# flarm-f4-interface.net
KiCad netlist of a schematic drawn in Altium Designer
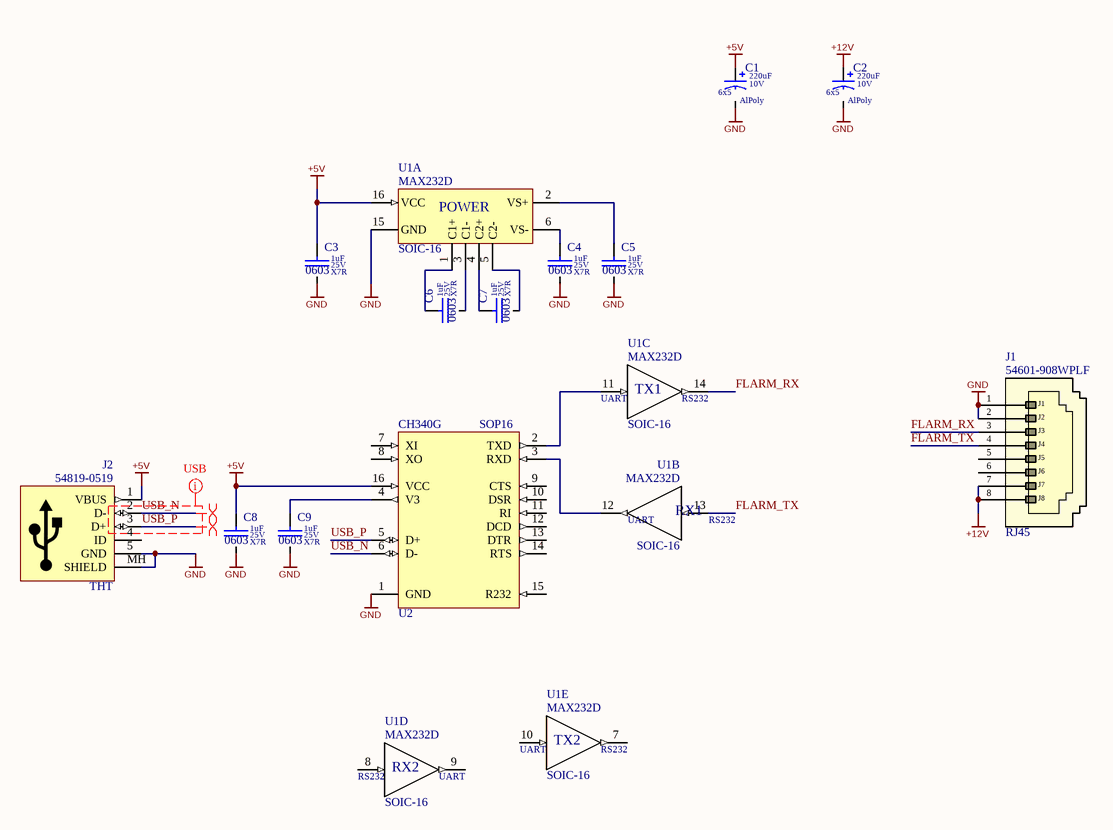
[diagram p0: flarm-f4-interface.SchDoc]

(export (version "E")
  (design (tool "Eeschema 10.0.6"))
  (components
    (comp (ref "C1")
      (value "220uF")
      (footprint "CE_D_6x5_SMD")
      (description "Polarized Capacitor")
      (fields
        (field (name "DIELECTRIC") "AlPoly")
        (field (name "SCH_FOOTPRINT") "6x5")
        (field (name "VOLTAGE") "10V")
        (field (name "PART NUMBER") "CE_220uF_10V_AlPoly_6x5_20")
        (field (name "MANUFACTURER") "Wurth Elektronik")
      )
      (libsource (lib "Library") (part "CE"))
    )
    (comp (ref "C2")
      (value "220uF")
      (footprint "CE_D_6x5_SMD")
      (description "Polarized Capacitor")
      (fields
        (field (name "DIELECTRIC") "AlPoly")
        (field (name "SCH_FOOTPRINT") "6x5")
        (field (name "VOLTAGE") "10V")
        (field (name "PART NUMBER") "CE_220uF_10V_AlPoly_6x5_20")
        (field (name "MANUFACTURER") "Wurth Elektronik")
      )
      (libsource (lib "Library") (part "CE"))
    )
    (comp (ref "C3")
      (value "1uF")
      (footprint "C_0603_1608")
      (description "Capacitor")
      (fields
        (field (name "DIELECTRIC") "X7R")
        (field (name "VOLTAGE") "25V")
        (field (name "SCH_FOOTPRINT") "0603")
        (field (name "PART NUMBER") "C_1uF_25V_X7R_0603_10")
        (field (name "MANUFACTURER") "Samsung")
      )
      (libsource (lib "Library") (part "C"))
    )
    (comp (ref "C4")
      (value "1uF")
      (footprint "C_0603_1608")
      (description "Capacitor")
      (fields
        (field (name "DIELECTRIC") "X7R")
        (field (name "VOLTAGE") "25V")
        (field (name "SCH_FOOTPRINT") "0603")
        (field (name "PART NUMBER") "C_1uF_25V_X7R_0603_10")
        (field (name "MANUFACTURER") "Samsung")
      )
      (libsource (lib "Library") (part "C"))
    )
    (comp (ref "C5")
      (value "1uF")
      (footprint "C_0603_1608")
      (description "Capacitor")
      (fields
        (field (name "DIELECTRIC") "X7R")
        (field (name "VOLTAGE") "25V")
        (field (name "SCH_FOOTPRINT") "0603")
        (field (name "PART NUMBER") "C_1uF_25V_X7R_0603_10")
        (field (name "MANUFACTURER") "Samsung")
      )
      (libsource (lib "Library") (part "C"))
    )
    (comp (ref "C6")
      (value "1uF")
      (footprint "C_0603_1608")
      (description "Capacitor")
      (fields
        (field (name "DIELECTRIC") "X7R")
        (field (name "VOLTAGE") "25V")
        (field (name "SCH_FOOTPRINT") "0603")
        (field (name "PART NUMBER") "C_1uF_25V_X7R_0603_10")
        (field (name "MANUFACTURER") "Samsung")
      )
      (libsource (lib "Library") (part "C"))
    )
    (comp (ref "C7")
      (value "1uF")
      (footprint "C_0603_1608")
      (description "Capacitor")
      (fields
        (field (name "DIELECTRIC") "X7R")
        (field (name "VOLTAGE") "25V")
        (field (name "SCH_FOOTPRINT") "0603")
        (field (name "PART NUMBER") "C_1uF_25V_X7R_0603_10")
        (field (name "MANUFACTURER") "Samsung")
      )
      (libsource (lib "Library") (part "C"))
    )
    (comp (ref "C8")
      (value "1uF")
      (footprint "C_0603_1608")
      (description "Capacitor")
      (fields
        (field (name "DIELECTRIC") "X7R")
        (field (name "VOLTAGE") "25V")
        (field (name "SCH_FOOTPRINT") "0603")
        (field (name "PART NUMBER") "C_1uF_25V_X7R_0603_10")
        (field (name "MANUFACTURER") "Samsung")
      )
      (libsource (lib "Library") (part "C"))
    )
    (comp (ref "C9")
      (value "1uF")
      (footprint "C_0603_1608")
      (description "Capacitor")
      (fields
        (field (name "DIELECTRIC") "X7R")
        (field (name "VOLTAGE") "25V")
        (field (name "SCH_FOOTPRINT") "0603")
        (field (name "PART NUMBER") "C_1uF_25V_X7R_0603_10")
        (field (name "MANUFACTURER") "Samsung")
      )
      (libsource (lib "Library") (part "C"))
    )
    (comp (ref "J1")
      (value "54601-908WPLF")
      (footprint "J_RJ45_54601-908WPLF")
      (fields
        (field (name "SCH_FOOTPRINT") "RJ45")
        (field (name "PART NUMBER") "J_RJ45_54601-908WPLF")
        (field (name "MANUFACTURER") "Amphenol")
        (field (name "Comment") "RJ45 without magnetics")
      )
      (libsource (lib "Library") (part "J_RJ45"))
    )
    (comp (ref "J2")
      (value "54819-0519")
      (footprint "J_USB_MINIB_54819-0519_THT")
      (description "USB A THT Connector")
      (fields
        (field (name "SCH_FOOTPRINT") "THT")
        (field (name "PART NUMBER") "J_USB_MINIB_54819-0519")
        (field (name "MANUFACTURER") "Molex")
      )
      (libsource (lib "Library") (part "J_USB_2.0_5pin"))
    )
    (comp (ref "U1")
      (value "MAX232D")
      (footprint "SOP16_SO16_SOIC16_4X10X6")
      (fields
        (field (name "SCH_FOOTPRINT") "SOIC-16")
        (field (name "PART NUMBER") "U_MAX232D")
        (field (name "MANUFACTURER") "Texas Instruments")
        (field (name "Comment") "MAX232D UART/RS-232 Converter")
      )
      (libsource (lib "Library") (part "U_MAX232D"))
    )
    (comp (ref "U2")
      (value "CH340G")
      (footprint "SOP16_SO16_SOIC16_4X10X6")
      (fields
        (field (name "SCH_FOOTPRINT") "SOP16")
        (field (name "PART NUMBER") "U_CH340G")
        (field (name "MANUFACTURER") "WCH")
        (field (name "Comment") "USB to serial chip")
      )
      (libsource (lib "Library") (part "U_CH340_MSOP16"))
    )
  )
  (nets
    (net (code "1") (name "+5V") (class "Default")
      (node (ref "C1") (pin "1") (pinfunction "1_1") (pintype "passive"))
      (node (ref "C3") (pin "1") (pinfunction "1_1") (pintype "passive"))
      (node (ref "C8") (pin "1") (pinfunction "1_1") (pintype "passive"))
      (node (ref "J2") (pin "1") (pinfunction "VBUS_1") (pintype "output"))
      (node (ref "U1") (pin "16") (pinfunction "VCC_16") (pintype "input"))
      (node (ref "U2") (pin "16") (pinfunction "VCC_16") (pintype "input"))
    )
    (net (code "2") (name "+12V") (class "Default")
      (node (ref "C2") (pin "1") (pinfunction "1_1") (pintype "passive"))
      (node (ref "J1") (pin "7") (pintype "passive"))
      (node (ref "J1") (pin "8") (pintype "passive"))
    )
    (net (code "3") (name "/FLARM_RX") (class "Default")
      (node (ref "J1") (pin "3") (pintype "passive"))
      (node (ref "U1") (pin "14") (pinfunction "T1OUT_14") (pintype "output"))
    )
    (net (code "4") (name "/FLARM_TX") (class "Default")
      (node (ref "J1") (pin "4") (pintype "passive"))
      (node (ref "U1") (pin "13") (pinfunction "R1IN_13") (pintype "input"))
    )
    (net (code "5") (name "/USB_N") (class "Default")
      (node (ref "J2") (pin "2") (pinfunction "D-_2") (pintype "bidirectional"))
      (node (ref "U2") (pin "6") (pinfunction "D-_6") (pintype "bidirectional"))
    )
    (net (code "6") (name "/USB_P") (class "Default")
      (node (ref "J2") (pin "3") (pinfunction "D+_3") (pintype "bidirectional"))
      (node (ref "U2") (pin "5") (pinfunction "D+_5") (pintype "bidirectional"))
    )
    (net (code "7") (name "GND") (class "Default")
      (node (ref "C1") (pin "2") (pinfunction "2_2") (pintype "passive"))
      (node (ref "C2") (pin "2") (pinfunction "2_2") (pintype "passive"))
      (node (ref "C3") (pin "2") (pinfunction "2_2") (pintype "passive"))
      (node (ref "C4") (pin "2") (pinfunction "2_2") (pintype "passive"))
      (node (ref "C5") (pin "2") (pinfunction "2_2") (pintype "passive"))
      (node (ref "C8") (pin "2") (pinfunction "2_2") (pintype "passive"))
      (node (ref "C9") (pin "2") (pinfunction "2_2") (pintype "passive"))
      (node (ref "J1") (pin "1") (pintype "passive"))
      (node (ref "J1") (pin "2") (pintype "passive"))
      (node (ref "J2") (pin "5") (pinfunction "GND_5") (pintype "power_in"))
      (node (ref "J2") (pin "MH") (pinfunction "SHIELD_MH") (pintype "passive"))
      (node (ref "U1") (pin "15") (pinfunction "GND_15") (pintype "power_in"))
      (node (ref "U2") (pin "1") (pinfunction "GND_1") (pintype "power_in"))
    )
    (net (code "8") (name "Net-(U1A-C1+)") (class "Default")
      (node (ref "C6") (pin "1") (pinfunction "1_1") (pintype "passive"))
      (node (ref "U1") (pin "1") (pinfunction "C1+_1") (pintype "passive"))
    )
    (net (code "9") (name "Net-(U1A-C1-)") (class "Default")
      (node (ref "C6") (pin "2") (pinfunction "2_2") (pintype "passive"))
      (node (ref "U1") (pin "3") (pinfunction "C1-_3") (pintype "passive"))
    )
    (net (code "10") (name "Net-(U1A-C2+)") (class "Default")
      (node (ref "C7") (pin "1") (pinfunction "1_1") (pintype "passive"))
      (node (ref "U1") (pin "4") (pinfunction "C2+_4") (pintype "passive"))
    )
    (net (code "11") (name "Net-(U1A-C2-)") (class "Default")
      (node (ref "C7") (pin "2") (pinfunction "2_2") (pintype "passive"))
      (node (ref "U1") (pin "5") (pinfunction "C2-_5") (pintype "passive"))
    )
    (net (code "12") (name "Net-(U1A-VS+)") (class "Default")
      (node (ref "C5") (pin "1") (pinfunction "1_1") (pintype "passive"))
      (node (ref "U1") (pin "2") (pinfunction "VS+_2") (pintype "passive"))
    )
    (net (code "13") (name "Net-(U1A-VS-)") (class "Default")
      (node (ref "C4") (pin "1") (pinfunction "1_1") (pintype "passive"))
      (node (ref "U1") (pin "6") (pinfunction "VS-_6") (pintype "passive"))
    )
    (net (code "14") (name "Net-(U1B-R1OUT)") (class "Default")
      (node (ref "U1") (pin "12") (pinfunction "R1OUT_12") (pintype "output"))
      (node (ref "U2") (pin "3") (pinfunction "RXD_3") (pintype "input"))
    )
    (net (code "15") (name "Net-(U1C-T1IN)") (class "Default")
      (node (ref "U1") (pin "11") (pinfunction "T1IN_11") (pintype "input"))
      (node (ref "U2") (pin "2") (pinfunction "TXD_2") (pintype "output"))
    )
    (net (code "16") (name "Net-(U2-V3)") (class "Default")
      (node (ref "C9") (pin "1") (pinfunction "1_1") (pintype "passive"))
      (node (ref "U2") (pin "4") (pinfunction "V3_4") (pintype "output"))
    )
    (net (code "17") (name "unconnected-(J1-Pad5)") (class "Default")
      (node (ref "J1") (pin "5") (pintype "passive"))
    )
    (net (code "18") (name "unconnected-(J1-Pad6)") (class "Default")
      (node (ref "J1") (pin "6") (pintype "passive"))
    )
    (net (code "19") (name "unconnected-(J2-ID-Pad4)") (class "Default")
      (node (ref "J2") (pin "4") (pinfunction "ID_4") (pintype "power_in"))
    )
    (net (code "20") (name "unconnected-(U1D-R2IN-Pad8)") (class "Default")
      (node (ref "U1") (pin "8") (pinfunction "R2IN_8") (pintype "input"))
    )
    (net (code "21") (name "unconnected-(U1D-R2OUT-Pad9)") (class "Default")
      (node (ref "U1") (pin "9") (pinfunction "R2OUT_9") (pintype "output"))
    )
    (net (code "22") (name "unconnected-(U1E-T2IN-Pad10)") (class "Default")
      (node (ref "U1") (pin "10") (pinfunction "T2IN_10") (pintype "input"))
    )
    (net (code "23") (name "unconnected-(U1E-T2OUT-Pad7)") (class "Default")
      (node (ref "U1") (pin "7") (pinfunction "T2OUT_7") (pintype "output"))
    )
    (net (code "24") (name "unconnected-(U2-CTS-Pad9)") (class "Default")
      (node (ref "U2") (pin "9") (pinfunction "CTS_9") (pintype "input"))
    )
    (net (code "25") (name "unconnected-(U2-DCD-Pad12)") (class "Default")
      (node (ref "U2") (pin "12") (pinfunction "DCD_12") (pintype "output"))
    )
    (net (code "26") (name "unconnected-(U2-DSR-Pad10)") (class "Default")
      (node (ref "U2") (pin "10") (pinfunction "DSR_10") (pintype "input"))
    )
    (net (code "27") (name "unconnected-(U2-DTR-Pad13)") (class "Default")
      (node (ref "U2") (pin "13") (pinfunction "DTR_13") (pintype "output"))
    )
    (net (code "28") (name "unconnected-(U2-R232-Pad15)") (class "Default")
      (node (ref "U2") (pin "15") (pinfunction "R232_15") (pintype "input"))
    )
    (net (code "29") (name "unconnected-(U2-RI-Pad11)") (class "Default")
      (node (ref "U2") (pin "11") (pinfunction "RI_11") (pintype "input"))
    )
    (net (code "30") (name "unconnected-(U2-RTS-Pad14)") (class "Default")
      (node (ref "U2") (pin "14") (pinfunction "RTS_14") (pintype "output"))
    )
    (net (code "31") (name "unconnected-(U2-XI-Pad7)") (class "Default")
      (node (ref "U2") (pin "7") (pinfunction "XI_7") (pintype "input"))
    )
    (net (code "32") (name "unconnected-(U2-XO-Pad8)") (class "Default")
      (node (ref "U2") (pin "8") (pinfunction "XO_8") (pintype "input"))
    )
  )
)
